# ud100v1.net
KiCad netlist of a schematic drawn in EAGLE
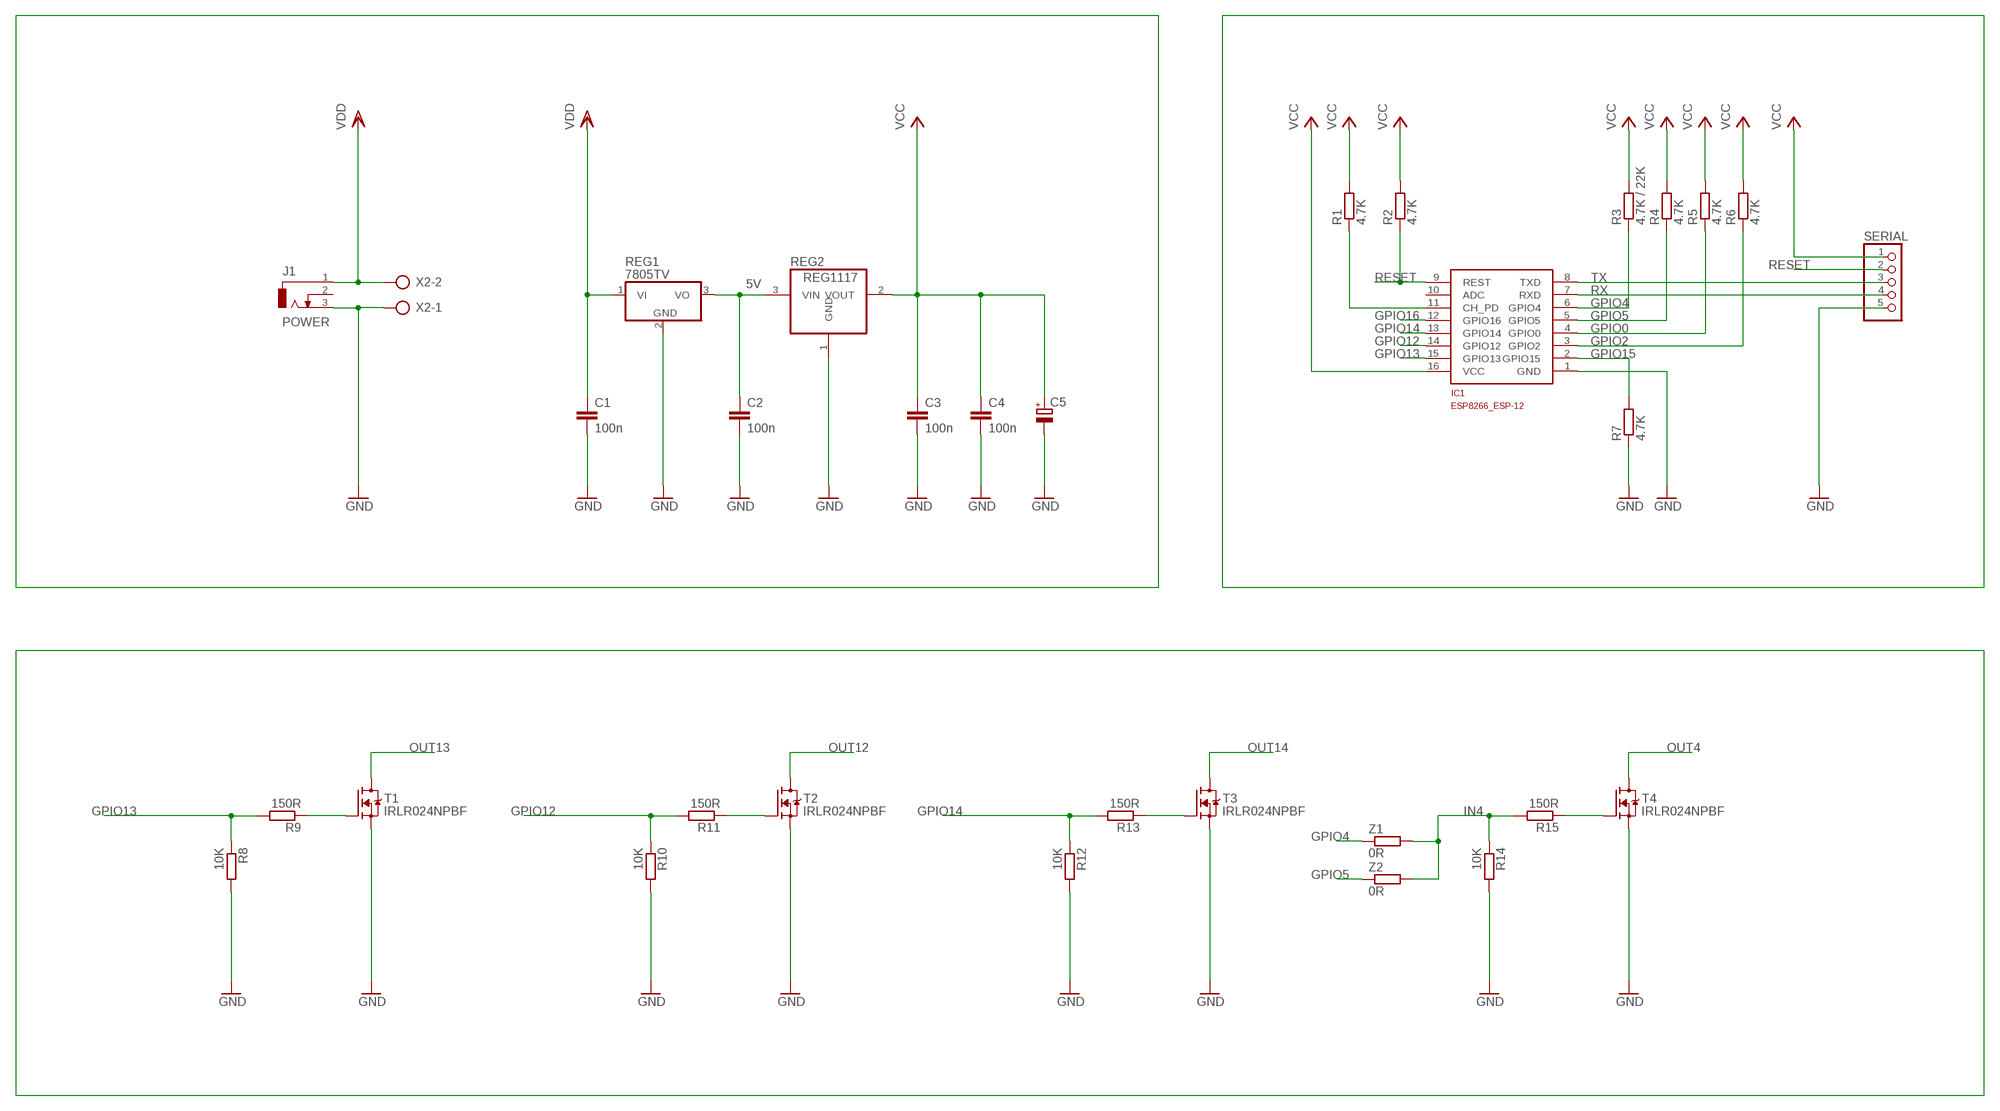
[diagram p0: schematic, sheet 1, part 1 of 2]
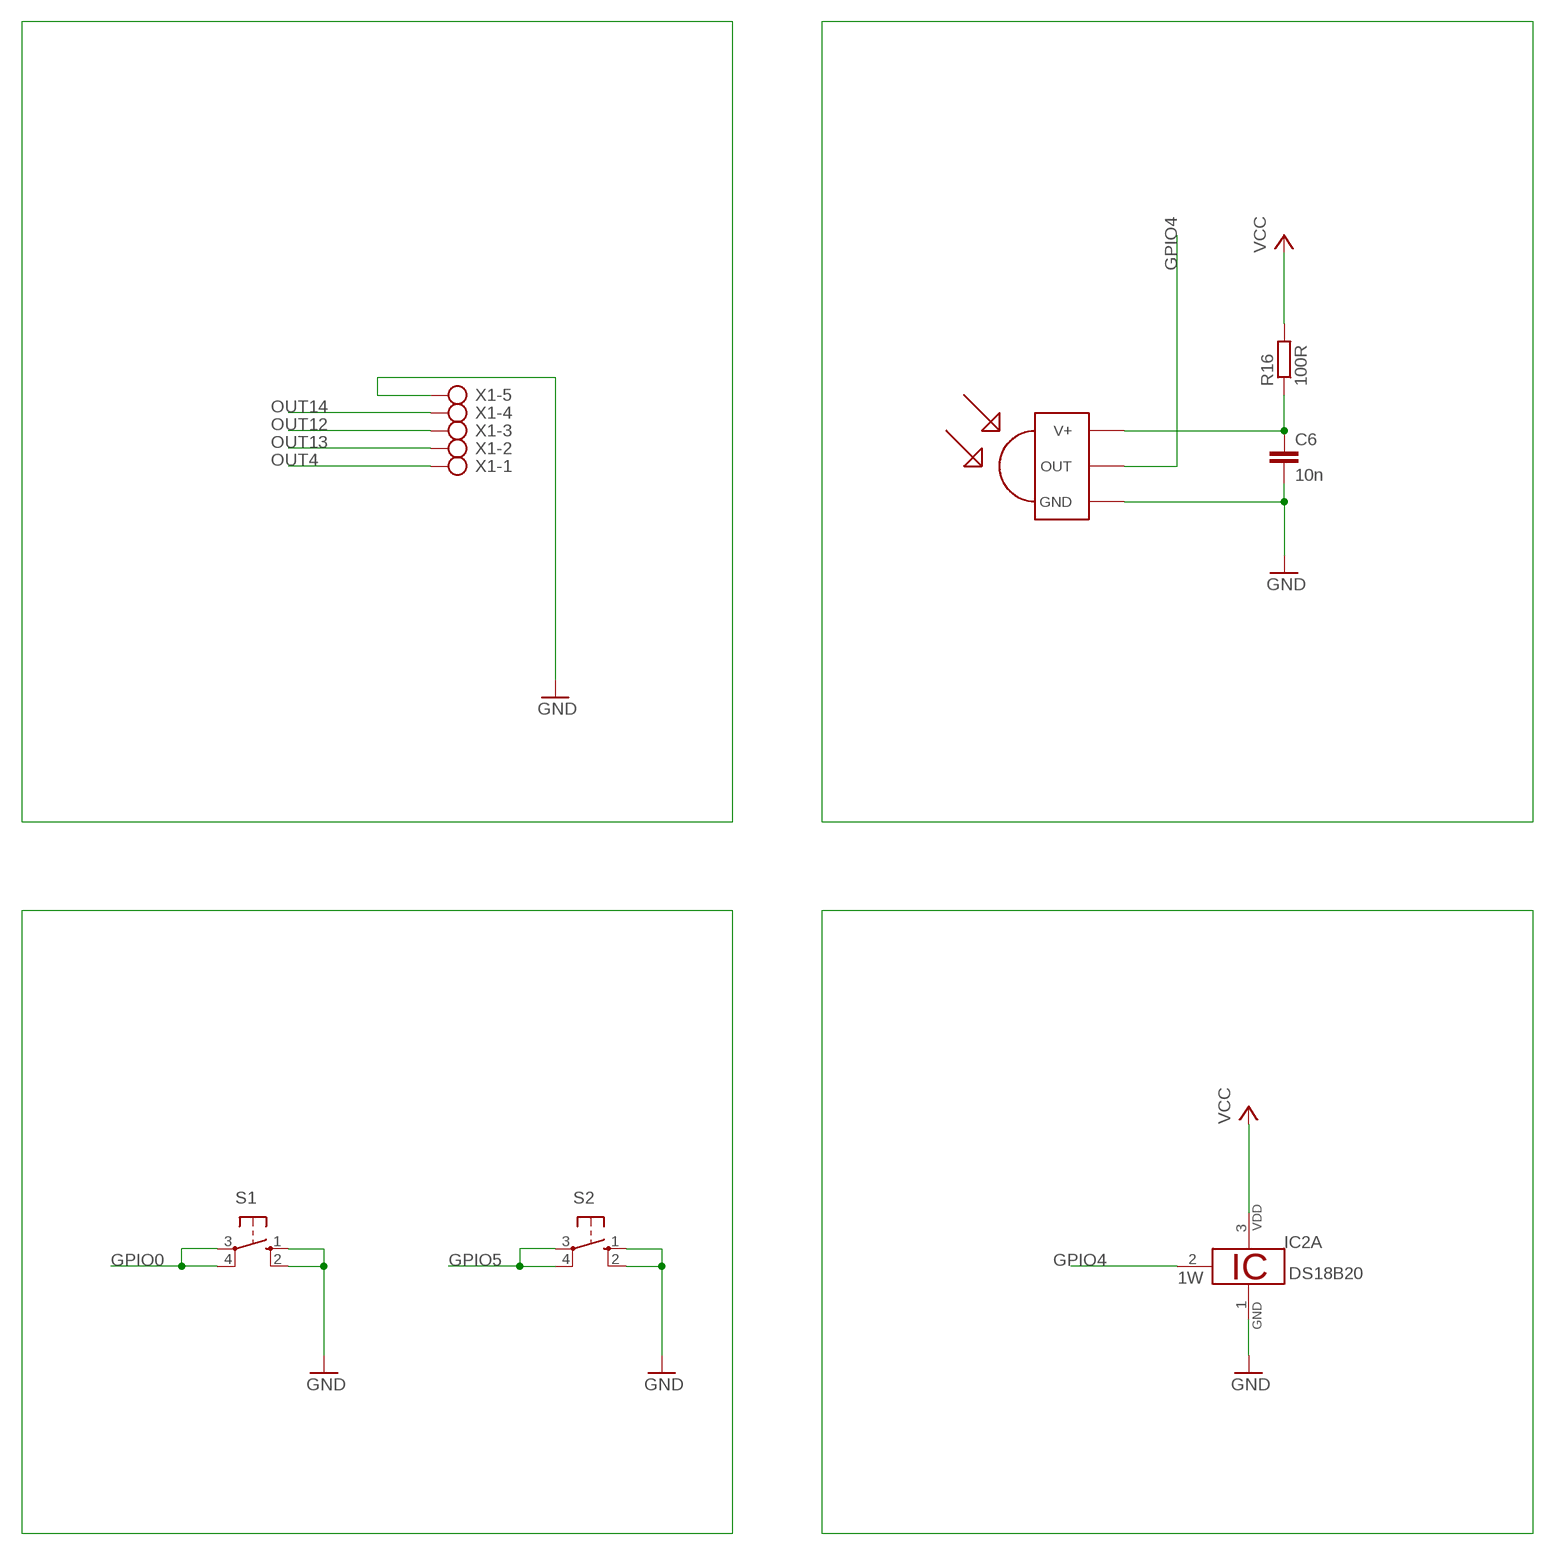
[diagram p1: schematic, sheet 1, part 2 of 2]

(export (version "E")
  (design (tool "Eeschema 10.0.6"))
  (components
    (comp (ref "C1")
      (value "100n")
      (footprint "eagle-import:C1206")
      (libsource (lib "eagle-import") (part "C-EUC1206"))
    )
    (comp (ref "C2")
      (value "100n")
      (footprint "eagle-import:C1206")
      (libsource (lib "eagle-import") (part "C-EUC1206"))
    )
    (comp (ref "C3")
      (value "100n")
      (footprint "eagle-import:C1206")
      (libsource (lib "eagle-import") (part "C-EUC1206"))
    )
    (comp (ref "C4")
      (value "100n")
      (footprint "eagle-import:C1206")
      (libsource (lib "eagle-import") (part "C-EUC1206"))
    )
    (comp (ref "C5")
      (value "CPOL-EUUD-6,3X8,8")
      (footprint "eagle-import:UD-6,3X5,8_NICHICON")
      (libsource (lib "eagle-import") (part "CPOL-EUUD-6,3X8,8"))
    )
    (comp (ref "C6")
      (value "10n")
      (footprint "eagle-import:C1206")
      (libsource (lib "eagle-import") (part "C-EUC1206"))
    )
    (comp (ref "IC1")
      (value "ESP8266_ESP-12")
      (footprint "eagle-import:ESP8266-ESP12")
      (libsource (lib "eagle-import") (part "ESP8266_ESP-12"))
    )
    (comp (ref "IC2")
      (value "DS18B20")
      (footprint "eagle-import:TO92-")
      (libsource (lib "eagle-import") (part "DS18B20"))
    )
    (comp (ref "J1")
      (value "POWER")
      (footprint "eagle-import:DCJ0303")
      (libsource (lib "eagle-import") (part "DCJ0303"))
    )
    (comp (ref "R1")
      (value "4.7K")
      (footprint "eagle-import:R1206")
      (libsource (lib "eagle-import") (part "R-EU_R1206"))
    )
    (comp (ref "R2")
      (value "4.7K")
      (footprint "eagle-import:R1206")
      (libsource (lib "eagle-import") (part "R-EU_R1206"))
    )
    (comp (ref "R3")
      (value "4.7K / 22K")
      (footprint "eagle-import:R1206")
      (libsource (lib "eagle-import") (part "R-EU_R1206"))
    )
    (comp (ref "R4")
      (value "4.7K")
      (footprint "eagle-import:R1206")
      (libsource (lib "eagle-import") (part "R-EU_R1206"))
    )
    (comp (ref "R5")
      (value "4.7K")
      (footprint "eagle-import:R1206")
      (libsource (lib "eagle-import") (part "R-EU_R1206"))
    )
    (comp (ref "R6")
      (value "4.7K")
      (footprint "eagle-import:R1206")
      (libsource (lib "eagle-import") (part "R-EU_R1206"))
    )
    (comp (ref "R7")
      (value "4.7K")
      (footprint "eagle-import:R1206")
      (libsource (lib "eagle-import") (part "R-EU_R1206"))
    )
    (comp (ref "R8")
      (value "10K")
      (footprint "eagle-import:R1206")
      (libsource (lib "eagle-import") (part "R-EU_R1206"))
    )
    (comp (ref "R9")
      (value "150R")
      (footprint "eagle-import:R1206")
      (libsource (lib "eagle-import") (part "R-EU_R1206"))
    )
    (comp (ref "R10")
      (value "10K")
      (footprint "eagle-import:R1206")
      (libsource (lib "eagle-import") (part "R-EU_R1206"))
    )
    (comp (ref "R11")
      (value "150R")
      (footprint "eagle-import:R1206")
      (libsource (lib "eagle-import") (part "R-EU_R1206"))
    )
    (comp (ref "R12")
      (value "10K")
      (footprint "eagle-import:R1206")
      (libsource (lib "eagle-import") (part "R-EU_R1206"))
    )
    (comp (ref "R13")
      (value "150R")
      (footprint "eagle-import:R1206")
      (libsource (lib "eagle-import") (part "R-EU_R1206"))
    )
    (comp (ref "R14")
      (value "10K")
      (footprint "eagle-import:R1206")
      (libsource (lib "eagle-import") (part "R-EU_R1206"))
    )
    (comp (ref "R15")
      (value "150R")
      (footprint "eagle-import:R1206")
      (libsource (lib "eagle-import") (part "R-EU_R1206"))
    )
    (comp (ref "R16")
      (value "100R")
      (footprint "eagle-import:R1206")
      (libsource (lib "eagle-import") (part "R-EU_R1206"))
    )
    (comp (ref "REG1")
      (value "7805TV")
      (footprint "eagle-import:TO220V")
      (libsource (lib "eagle-import") (part "78TV05"))
    )
    (comp (ref "REG2")
      (value "REG1117")
      (footprint "eagle-import:SOT223")
      (libsource (lib "eagle-import") (part "REG1117"))
    )
    (comp (ref "S1")
      (value "10-XX")
      (footprint "eagle-import:B3F-10XX")
      (fields (field (name "MPN") "B3F-1000"))
      (libsource (lib "eagle-import") (part "10-XX"))
    )
    (comp (ref "S2")
      (value "10-XX")
      (footprint "eagle-import:B3F-10XX")
      (fields (field (name "MPN") "B3F-1000"))
      (libsource (lib "eagle-import") (part "10-XX"))
    )
    (comp (ref "SERIAL")
      (value "PINHD-1X5")
      (footprint "eagle-import:1X05")
      (libsource (lib "eagle-import") (part "PINHD-1X5"))
    )
    (comp (ref "T1")
      (value "IRLR024NPBF")
      (footprint "eagle-import:DPAK_TO252")
      (libsource (lib "eagle-import") (part "MOSFET-N-DPAK"))
    )
    (comp (ref "T2")
      (value "IRLR024NPBF")
      (footprint "eagle-import:DPAK_TO252")
      (libsource (lib "eagle-import") (part "MOSFET-N-DPAK"))
    )
    (comp (ref "T3")
      (value "IRLR024NPBF")
      (footprint "eagle-import:DPAK_TO252")
      (libsource (lib "eagle-import") (part "MOSFET-N-DPAK"))
    )
    (comp (ref "T4")
      (value "IRLR024NPBF")
      (footprint "eagle-import:DPAK_TO252")
      (libsource (lib "eagle-import") (part "MOSFET-N-DPAK"))
    )
    (comp (ref "U$1")
      (value "TSOP1736")
      (footprint "eagle-import:TSOP17XX")
      (libsource (lib "eagle-import") (part "TSOP1736"))
    )
    (comp (ref "X1")
      (value "AK500/5")
      (footprint "eagle-import:AK500_5")
      (libsource (lib "eagle-import") (part "AK500/5"))
    )
    (comp (ref "X2")
      (value "AK500/2")
      (footprint "eagle-import:AK500_2")
      (libsource (lib "eagle-import") (part "AK500/2"))
    )
    (comp (ref "Z1")
      (value "0R")
      (footprint "eagle-import:R0805")
      (libsource (lib "eagle-import") (part "R-EU_R0805"))
    )
    (comp (ref "Z2")
      (value "0R")
      (footprint "eagle-import:R0805")
      (libsource (lib "eagle-import") (part "R-EU_R0805"))
    )
  )
  (nets
    (net (code "1") (name "/5V") (class "Default")
      (node (ref "C2") (pin "1") (pinfunction "1_1") (pintype "passive"))
      (node (ref "REG1") (pin "3") (pinfunction "VO_3") (pintype "passive"))
      (node (ref "REG2") (pin "3") (pinfunction "VIN_3") (pintype "input"))
    )
    (net (code "2") (name "/GPIO0") (class "Default")
      (node (ref "IC1") (pin "4") (pinfunction "GPIO0_4") (pintype "bidirectional"))
      (node (ref "R5") (pin "1") (pinfunction "1_1") (pintype "passive"))
      (node (ref "S1") (pin "3") (pinfunction "P_3") (pintype "passive"))
      (node (ref "S1") (pin "4") (pinfunction "P1_4") (pintype "passive"))
    )
    (net (code "3") (name "/GPIO2") (class "Default")
      (node (ref "IC1") (pin "3") (pinfunction "GPIO2_3") (pintype "bidirectional"))
      (node (ref "R6") (pin "1") (pinfunction "1_1") (pintype "passive"))
    )
    (net (code "4") (name "/GPIO4") (class "Default")
      (node (ref "IC1") (pin "6") (pinfunction "GPIO4_6") (pintype "bidirectional"))
      (node (ref "IC2") (pin "2") (pinfunction "1W_2") (pintype "power_in"))
      (node (ref "R3") (pin "1") (pinfunction "1_1") (pintype "passive"))
      (node (ref "U$1") (pin "OUT") (pinfunction "OUT_OUT") (pintype "bidirectional"))
      (node (ref "Z1") (pin "1") (pinfunction "1_1") (pintype "passive"))
    )
    (net (code "5") (name "/GPIO5") (class "Default")
      (node (ref "IC1") (pin "5") (pinfunction "GPIO5_5") (pintype "bidirectional"))
      (node (ref "R4") (pin "1") (pinfunction "1_1") (pintype "passive"))
      (node (ref "S2") (pin "3") (pinfunction "P_3") (pintype "passive"))
      (node (ref "S2") (pin "4") (pinfunction "P1_4") (pintype "passive"))
      (node (ref "Z2") (pin "1") (pinfunction "1_1") (pintype "passive"))
    )
    (net (code "6") (name "/GPIO12") (class "Default")
      (node (ref "IC1") (pin "14") (pinfunction "GPIO12_14") (pintype "bidirectional"))
      (node (ref "R10") (pin "1") (pinfunction "1_1") (pintype "passive"))
      (node (ref "R11") (pin "2") (pinfunction "2_2") (pintype "passive"))
    )
    (net (code "7") (name "/GPIO13") (class "Default")
      (node (ref "IC1") (pin "15") (pinfunction "GPIO13_15") (pintype "bidirectional"))
      (node (ref "R8") (pin "1") (pinfunction "1_1") (pintype "passive"))
      (node (ref "R9") (pin "2") (pinfunction "2_2") (pintype "passive"))
    )
    (net (code "8") (name "/GPIO14") (class "Default")
      (node (ref "IC1") (pin "13") (pinfunction "GPIO14_13") (pintype "bidirectional"))
      (node (ref "R12") (pin "1") (pinfunction "1_1") (pintype "passive"))
      (node (ref "R13") (pin "2") (pinfunction "2_2") (pintype "passive"))
    )
    (net (code "9") (name "/GPIO15") (class "Default")
      (node (ref "IC1") (pin "2") (pinfunction "GPIO15_2") (pintype "bidirectional"))
      (node (ref "R7") (pin "2") (pinfunction "2_2") (pintype "passive"))
    )
    (net (code "10") (name "/GPIO16") (class "Default")
      (node (ref "IC1") (pin "12") (pinfunction "GPIO16_12") (pintype "bidirectional"))
    )
    (net (code "11") (name "/IN4") (class "Default")
      (node (ref "R14") (pin "1") (pinfunction "1_1") (pintype "passive"))
      (node (ref "R15") (pin "2") (pinfunction "2_2") (pintype "passive"))
      (node (ref "Z1") (pin "2") (pinfunction "2_2") (pintype "passive"))
      (node (ref "Z2") (pin "2") (pinfunction "2_2") (pintype "passive"))
    )
    (net (code "12") (name "/OUT4") (class "Default")
      (node (ref "T4") (pin "2") (pinfunction "D_2") (pintype "passive"))
      (node (ref "X1") (pin "1") (pinfunction "KL_1") (pintype "passive"))
    )
    (net (code "13") (name "/OUT12") (class "Default")
      (node (ref "T2") (pin "2") (pinfunction "D_2") (pintype "passive"))
      (node (ref "X1") (pin "3") (pinfunction "KL_3") (pintype "passive"))
    )
    (net (code "14") (name "/OUT13") (class "Default")
      (node (ref "T1") (pin "2") (pinfunction "D_2") (pintype "passive"))
      (node (ref "X1") (pin "2") (pinfunction "KL_2") (pintype "passive"))
    )
    (net (code "15") (name "/OUT14") (class "Default")
      (node (ref "T3") (pin "2") (pinfunction "D_2") (pintype "passive"))
      (node (ref "X1") (pin "4") (pinfunction "KL_4") (pintype "passive"))
    )
    (net (code "16") (name "/RESET") (class "Default")
      (node (ref "IC1") (pin "9") (pinfunction "REST_9") (pintype "bidirectional"))
      (node (ref "R2") (pin "1") (pinfunction "1_1") (pintype "passive"))
      (node (ref "SERIAL") (pin "2") (pinfunction "2_2") (pintype "passive"))
    )
    (net (code "17") (name "/RX") (class "Default")
      (node (ref "IC1") (pin "7") (pinfunction "RXD_7") (pintype "bidirectional"))
      (node (ref "SERIAL") (pin "4") (pinfunction "4_4") (pintype "passive"))
    )
    (net (code "18") (name "/TX") (class "Default")
      (node (ref "IC1") (pin "8") (pinfunction "TXD_8") (pintype "bidirectional"))
      (node (ref "SERIAL") (pin "3") (pinfunction "3_3") (pintype "passive"))
    )
    (net (code "19") (name "GND") (class "Default")
      (node (ref "C1") (pin "2") (pinfunction "2_2") (pintype "passive"))
      (node (ref "C2") (pin "2") (pinfunction "2_2") (pintype "passive"))
      (node (ref "C3") (pin "2") (pinfunction "2_2") (pintype "passive"))
      (node (ref "C4") (pin "2") (pinfunction "2_2") (pintype "passive"))
      (node (ref "C5") (pin "-") (pinfunction "-_-") (pintype "passive"))
      (node (ref "C6") (pin "2") (pinfunction "2_2") (pintype "passive"))
      (node (ref "IC1") (pin "1") (pinfunction "GND_1") (pintype "bidirectional"))
      (node (ref "IC2") (pin "1") (pinfunction "GND_1") (pintype "power_in"))
      (node (ref "J1") (pin "3") (pinfunction "3_3") (pintype "passive"))
      (node (ref "R10") (pin "2") (pinfunction "2_2") (pintype "passive"))
      (node (ref "R12") (pin "2") (pinfunction "2_2") (pintype "passive"))
      (node (ref "R14") (pin "2") (pinfunction "2_2") (pintype "passive"))
      (node (ref "R7") (pin "1") (pinfunction "1_1") (pintype "passive"))
      (node (ref "R8") (pin "2") (pinfunction "2_2") (pintype "passive"))
      (node (ref "REG1") (pin "2") (pinfunction "GND_2") (pintype "passive"))
      (node (ref "REG2") (pin "1") (pinfunction "GND_1") (pintype "power_in"))
      (node (ref "S1") (pin "1") (pinfunction "S_1") (pintype "passive"))
      (node (ref "S1") (pin "2") (pinfunction "S1_2") (pintype "passive"))
      (node (ref "S2") (pin "1") (pinfunction "S_1") (pintype "passive"))
      (node (ref "S2") (pin "2") (pinfunction "S1_2") (pintype "passive"))
      (node (ref "SERIAL") (pin "5") (pinfunction "5_5") (pintype "passive"))
      (node (ref "T1") (pin "3") (pinfunction "S_3") (pintype "passive"))
      (node (ref "T2") (pin "3") (pinfunction "S_3") (pintype "passive"))
      (node (ref "T3") (pin "3") (pinfunction "S_3") (pintype "passive"))
      (node (ref "T4") (pin "3") (pinfunction "S_3") (pintype "passive"))
      (node (ref "U$1") (pin "GND") (pinfunction "GND_GND") (pintype "bidirectional"))
      (node (ref "X1") (pin "5") (pinfunction "KL_5") (pintype "passive"))
      (node (ref "X2") (pin "1") (pinfunction "KL_1") (pintype "passive"))
    )
    (net (code "20") (name "Net-(C6-Pad1)") (class "Default")
      (node (ref "C6") (pin "1") (pinfunction "1_1") (pintype "passive"))
      (node (ref "R16") (pin "1") (pinfunction "1_1") (pintype "passive"))
      (node (ref "U$1") (pin "V+") (pinfunction "V+_V+") (pintype "bidirectional"))
    )
    (net (code "21") (name "Net-(IC1-CH_PD)") (class "Default")
      (node (ref "IC1") (pin "11") (pinfunction "CH_PD_11") (pintype "bidirectional"))
      (node (ref "R1") (pin "1") (pinfunction "1_1") (pintype "passive"))
    )
    (net (code "22") (name "Net-(T1-G)") (class "Default")
      (node (ref "R9") (pin "1") (pinfunction "1_1") (pintype "passive"))
      (node (ref "T1") (pin "1") (pinfunction "G_1") (pintype "passive"))
    )
    (net (code "23") (name "Net-(T2-G)") (class "Default")
      (node (ref "R11") (pin "1") (pinfunction "1_1") (pintype "passive"))
      (node (ref "T2") (pin "1") (pinfunction "G_1") (pintype "passive"))
    )
    (net (code "24") (name "Net-(T3-G)") (class "Default")
      (node (ref "R13") (pin "1") (pinfunction "1_1") (pintype "passive"))
      (node (ref "T3") (pin "1") (pinfunction "G_1") (pintype "passive"))
    )
    (net (code "25") (name "Net-(T4-G)") (class "Default")
      (node (ref "R15") (pin "1") (pinfunction "1_1") (pintype "passive"))
      (node (ref "T4") (pin "1") (pinfunction "G_1") (pintype "passive"))
    )
    (net (code "26") (name "VCC") (class "Default")
      (node (ref "C3") (pin "1") (pinfunction "1_1") (pintype "passive"))
      (node (ref "C4") (pin "1") (pinfunction "1_1") (pintype "passive"))
      (node (ref "C5") (pin "+") (pinfunction "+_+") (pintype "passive"))
      (node (ref "IC1") (pin "16") (pinfunction "VCC_16") (pintype "bidirectional"))
      (node (ref "IC2") (pin "3") (pinfunction "VDD_3") (pintype "power_in"))
      (node (ref "R1") (pin "2") (pinfunction "2_2") (pintype "passive"))
      (node (ref "R16") (pin "2") (pinfunction "2_2") (pintype "passive"))
      (node (ref "R2") (pin "2") (pinfunction "2_2") (pintype "passive"))
      (node (ref "R3") (pin "2") (pinfunction "2_2") (pintype "passive"))
      (node (ref "R4") (pin "2") (pinfunction "2_2") (pintype "passive"))
      (node (ref "R5") (pin "2") (pinfunction "2_2") (pintype "passive"))
      (node (ref "R6") (pin "2") (pinfunction "2_2") (pintype "passive"))
      (node (ref "REG2") (pin "2") (pinfunction "VOUT_2") (pintype "output"))
      (node (ref "SERIAL") (pin "1") (pinfunction "1_1") (pintype "passive"))
    )
    (net (code "27") (name "VDD") (class "Default")
      (node (ref "C1") (pin "1") (pinfunction "1_1") (pintype "passive"))
      (node (ref "J1") (pin "1") (pinfunction "1_1") (pintype "passive"))
      (node (ref "REG1") (pin "1") (pinfunction "VI_1") (pintype "input"))
      (node (ref "X2") (pin "2") (pinfunction "KL_2") (pintype "passive"))
    )
    (net (code "28") (name "unconnected-(IC1-ADC-Pad10)") (class "Default")
      (node (ref "IC1") (pin "10") (pinfunction "ADC_10") (pintype "bidirectional"))
    )
    (net (code "29") (name "unconnected-(J1-Pad2)") (class "Default")
      (node (ref "J1") (pin "2") (pinfunction "2_2") (pintype "passive"))
    )
  )
)
